# TSC_AD7843.net
KiCad netlist of a schematic drawn in Altium Designer
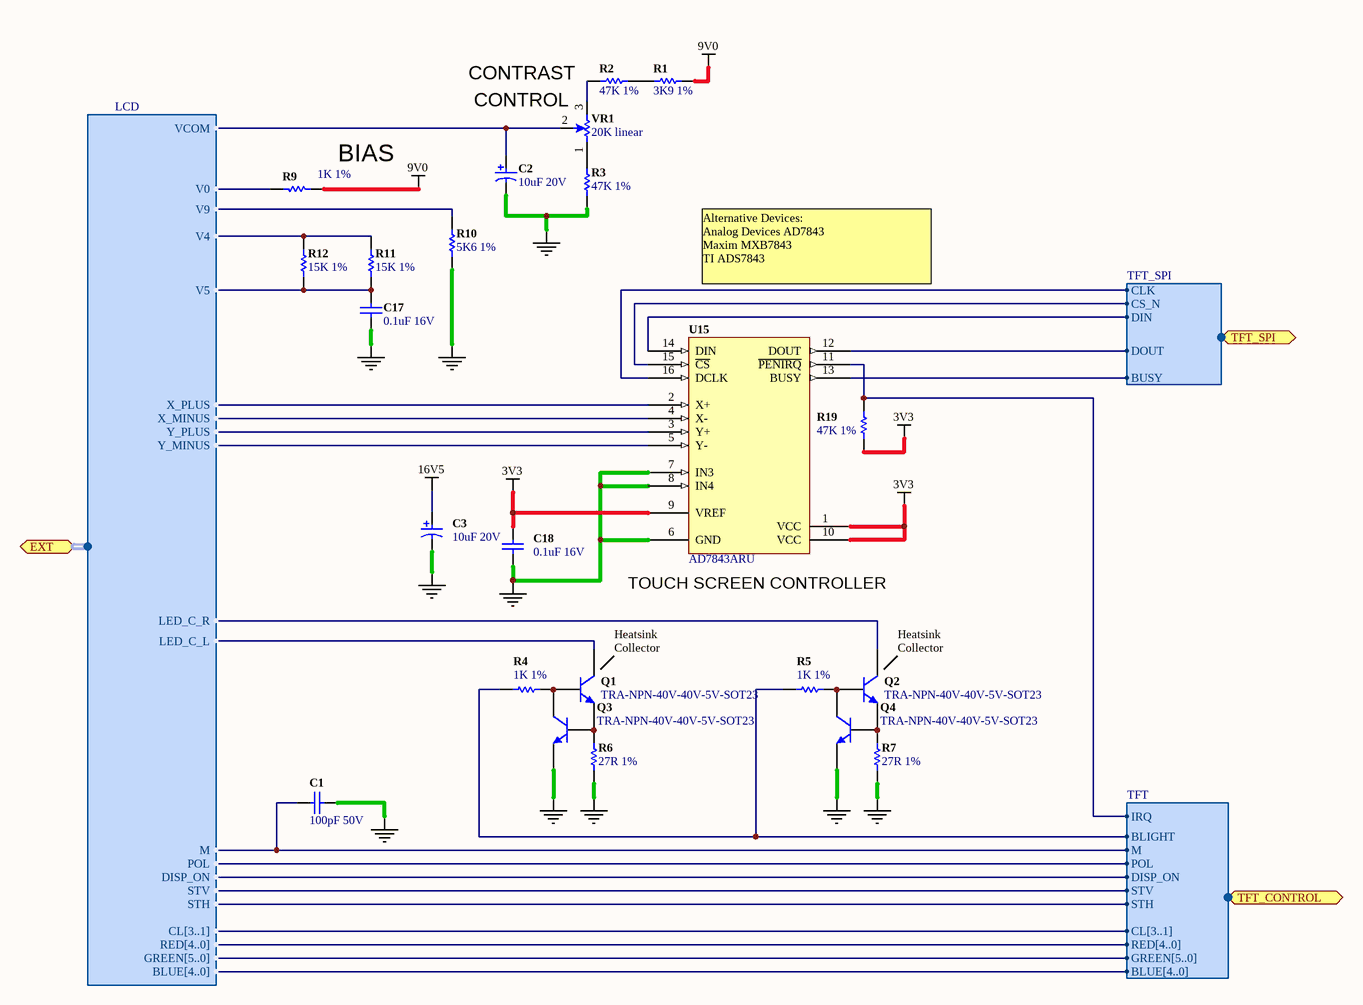
[diagram p0: TSC_AD7843.SchDoc]

(export (version "E")
  (design (tool "Eeschema 10.0.6"))
  (components
    (comp (ref "C1")
      (value "100pF 50V")
      (footprint "CAPC1005-STAR")
      (description "Capacitor, Ceramic, 100pF 5% 50V 0402 (1005) COG")
      (fields (field (name "TOLERANCE") "5 %"))
      (libsource (lib "altium-import") (part "root_3_mirrored_CAP-NP_"))
    )
    (comp (ref "C2")
      (value "10uF 20V")
      (footprint "CAPC3528-STAR")
      (description "Capacitor, Tantalum, 10uF 10% 20V MCCT-B (3528)")
      (fields (field (name "TOLERANCE") "10 %"))
      (libsource (lib "altium-import") (part "root_0_CAP-P_"))
    )
    (comp (ref "C3")
      (value "10uF 20V")
      (footprint "CAPC3528-STAR")
      (description "Capacitor, Tantalum, 10uF 10% 20V MCCT-B (3528)")
      (fields (field (name "TOLERANCE") "10 %"))
      (libsource (lib "altium-import") (part "root_0_CAP-P_"))
    )
    (comp (ref "C17")
      (value "0.1uF 16V")
      (footprint "CAPC1005-STAR")
      (description "Capacitor, Ceramic, 0.1uF 10% 16V 0402 (1005) X7R")
      (fields (field (name "TOLERANCE") "10 %"))
      (libsource (lib "altium-import") (part "root_0_mirrored_CAP-NP_"))
    )
    (comp (ref "C18")
      (value "0.1uF 16V")
      (footprint "CAPC1005-STAR")
      (description "Capacitor, Ceramic, 0.1uF 10% 16V 0402 (1005) X7R")
      (fields (field (name "TOLERANCE") "10 %"))
      (libsource (lib "altium-import") (part "root_0_CAP-NP_"))
    )
    (comp (ref "Q1")
      (value "TRA-NPN-40V-40V-5V-SOT23")
      (footprint "SOT95P230-3C")
      (description "Transistor, FMMT491A Small Signal NPN")
      (libsource (lib "altium-import") (part "root_0_TRA-NPN_"))
    )
    (comp (ref "Q2")
      (value "TRA-NPN-40V-40V-5V-SOT23")
      (footprint "SOT95P230-3C")
      (description "Transistor, FMMT491A Small Signal NPN")
      (libsource (lib "altium-import") (part "root_0_TRA-NPN_"))
    )
    (comp (ref "Q3")
      (value "TRA-NPN-40V-40V-5V-SOT23")
      (footprint "SOT95P230-3C")
      (description "Transistor, FMMT491A Small Signal NPN")
      (libsource (lib "altium-import") (part "root_0_mirrored_TRA-NPN_"))
    )
    (comp (ref "Q4")
      (value "TRA-NPN-40V-40V-5V-SOT23")
      (footprint "SOT95P230-3C")
      (description "Transistor, FMMT491A Small Signal NPN")
      (libsource (lib "altium-import") (part "root_0_mirrored_TRA-NPN_"))
    )
    (comp (ref "R1")
      (value "3K9 1%")
      (footprint "RESC1005-STAR")
      (description "Resistor, 3K9 1% 0402 (1005)")
      (fields (field (name "TOLERANCE") "1 %"))
      (libsource (lib "altium-import") (part "root_1_RES_"))
    )
    (comp (ref "R2")
      (value "47K 1%")
      (footprint "RESC1005-STAR")
      (description "Resistor, 47K 1% 0402 (1005)")
      (fields (field (name "TOLERANCE") "1 %"))
      (libsource (lib "altium-import") (part "root_1_RES_"))
    )
    (comp (ref "R3")
      (value "47K 1%")
      (footprint "RESC1005-STAR")
      (description "Resistor, 47K 1% 0402 (1005)")
      (fields (field (name "TOLERANCE") "1 %"))
      (libsource (lib "altium-import") (part "root_2_RES_"))
    )
    (comp (ref "R4")
      (value "1K 1%")
      (footprint "RESC1005-STAR")
      (description "Resistor, 1K 1% 0402 (1005)")
      (fields (field (name "TOLERANCE") "1 %"))
      (libsource (lib "altium-import") (part "root_1_RES_"))
    )
    (comp (ref "R5")
      (value "1K 1%")
      (footprint "RESC1005-STAR")
      (description "Resistor, 1K 1% 0402 (1005)")
      (fields (field (name "TOLERANCE") "1 %"))
      (libsource (lib "altium-import") (part "root_1_RES_"))
    )
    (comp (ref "R6")
      (value "27R 1%")
      (footprint "RESC1005-STAR")
      (description "Resistor, 27R 1% 0402 (1005)")
      (fields (field (name "TOLERANCE") "1 %"))
      (libsource (lib "altium-import") (part "root_2_RES_"))
    )
    (comp (ref "R7")
      (value "27R 1%")
      (footprint "RESC1005-STAR")
      (description "Resistor, 27R 1% 0402 (1005)")
      (fields (field (name "TOLERANCE") "1 %"))
      (libsource (lib "altium-import") (part "root_2_RES_"))
    )
    (comp (ref "R9")
      (value "1K 1%")
      (footprint "RESC1005-STAR")
      (description "Resistor, 1K 1% 0402 (1005)")
      (fields (field (name "TOLERANCE") "1 %"))
      (libsource (lib "altium-import") (part "root_3_mirrored_RES_"))
    )
    (comp (ref "R10")
      (value "5K6 1%")
      (footprint "RESC1005-STAR")
      (description "Resistor, 5K6 1% 0402 (1005)")
      (fields (field (name "TOLERANCE") "1 %"))
      (libsource (lib "altium-import") (part "root_2_RES_"))
    )
    (comp (ref "R11")
      (value "15K 1%")
      (footprint "RESC1005-STAR")
      (description "Resistor, 15K 1% 0402 (1005)")
      (fields (field (name "TOLERANCE") "1 %"))
      (libsource (lib "altium-import") (part "root_2_RES_"))
    )
    (comp (ref "R12")
      (value "15K 1%")
      (footprint "RESC1005-STAR")
      (description "Resistor, 15K 1% 0402 (1005)")
      (fields (field (name "TOLERANCE") "1 %"))
      (libsource (lib "altium-import") (part "root_2_RES_"))
    )
    (comp (ref "R19")
      (value "47K 1%")
      (footprint "RESC1005-STAR")
      (description "Resistor, 47K 1% 0402 (1005)")
      (fields (field (name "TOLERANCE") "1 %"))
      (libsource (lib "altium-import") (part "root_0_RES_"))
    )
    (comp (ref "U15")
      (value "AD7843ARU")
      (footprint "TSOP65P638-16")
      (description "AD7843ARU,12-bit SPI Touch Screen Digitizer")
      (libsource (lib "altium-import") (part "root_0_AD7843ARU_"))
    )
    (comp (ref "VR1")
      (value "20K linear")
      (footprint "TRIM_3314J-1-203E")
      (description "Potentiometer, 20K 4mm Cermet PCB SMT Trimmer")
      (libsource (lib "altium-import") (part "root_2_mirrored_POT_"))
    )
  )
  (nets
    (net (code "5") (name "/BLIGHT") (class "Default")
      (node (ref "R4") (pin "1") (pinfunction "1_1") (pintype "passive"))
      (node (ref "R5") (pin "1") (pinfunction "1_1") (pintype "passive"))
    )
    (net (code "6") (name "/BUSY") (class "Default")
      (node (ref "U15") (pin "13") (pinfunction "BUSY_13") (pintype "output"))
    )
    (net (code "7") (name "/CLK") (class "Default")
      (node (ref "U15") (pin "16") (pinfunction "DCLK_16") (pintype "input"))
    )
    (net (code "8") (name "/CS_N") (class "Default")
      (node (ref "U15") (pin "15") (pinfunction "~{CS}_15") (pintype "input"))
    )
    (net (code "9") (name "/DIN") (class "Default")
      (node (ref "U15") (pin "14") (pinfunction "DIN_14") (pintype "input"))
    )
    (net (code "11") (name "/DOUT") (class "Default")
      (node (ref "U15") (pin "12") (pinfunction "DOUT_12") (pintype "output"))
    )
    (net (code "13") (name "/IRQ") (class "Default")
      (node (ref "R19") (pin "1") (pinfunction "1_1") (pintype "passive"))
      (node (ref "U15") (pin "11") (pinfunction "~{PENIRQ}_11") (pintype "output"))
    )
    (net (code "14") (name "/LED_C_L") (class "Default")
      (node (ref "Q1") (pin "3") (pinfunction "C_3") (pintype "passive"))
    )
    (net (code "15") (name "/LED_C_R") (class "Default")
      (node (ref "Q2") (pin "3") (pinfunction "C_3") (pintype "passive"))
    )
    (net (code "16") (name "/M") (class "Default")
      (node (ref "C1") (pin "1") (pinfunction "1_1") (pintype "passive"))
    )
    (net (code "21") (name "/V0") (class "Default")
      (node (ref "R9") (pin "1") (pinfunction "1_1") (pintype "passive"))
    )
    (net (code "22") (name "/V4") (class "Default")
      (node (ref "R11") (pin "2") (pinfunction "2_2") (pintype "passive"))
      (node (ref "R12") (pin "2") (pinfunction "2_2") (pintype "passive"))
    )
    (net (code "23") (name "/V5") (class "Default")
      (node (ref "C17") (pin "1") (pinfunction "1_1") (pintype "passive"))
      (node (ref "R11") (pin "1") (pinfunction "1_1") (pintype "passive"))
      (node (ref "R12") (pin "1") (pinfunction "1_1") (pintype "passive"))
    )
    (net (code "24") (name "/V9") (class "Default")
      (node (ref "R10") (pin "2") (pinfunction "2_2") (pintype "passive"))
    )
    (net (code "25") (name "/VCOM") (class "Default")
      (node (ref "C2") (pin "1") (pinfunction "1_1") (pintype "passive"))
      (node (ref "VR1") (pin "2") (pinfunction "2_2") (pintype "passive"))
    )
    (net (code "26") (name "/X_MINUS") (class "Default")
      (node (ref "U15") (pin "4") (pinfunction "X-_4") (pintype "input"))
    )
    (net (code "27") (name "/X_PLUS") (class "Default")
      (node (ref "U15") (pin "2") (pinfunction "X+_2") (pintype "input"))
    )
    (net (code "28") (name "/Y_MINUS") (class "Default")
      (node (ref "U15") (pin "5") (pinfunction "Y-_5") (pintype "input"))
    )
    (net (code "29") (name "/Y_PLUS") (class "Default")
      (node (ref "U15") (pin "3") (pinfunction "Y+_3") (pintype "input"))
    )
    (net (code "32") (name "3V3") (class "Default")
      (node (ref "C18") (pin "1") (pinfunction "1_1") (pintype "passive"))
      (node (ref "R19") (pin "2") (pinfunction "2_2") (pintype "passive"))
      (node (ref "U15") (pin "1") (pinfunction "VCC_1") (pintype "power_in"))
      (node (ref "U15") (pin "10") (pinfunction "VCC_10") (pintype "power_in"))
      (node (ref "U15") (pin "9") (pinfunction "VREF_9") (pintype "passive"))
    )
    (net (code "33") (name "9V0") (class "Default")
      (node (ref "R1") (pin "2") (pinfunction "2_2") (pintype "passive"))
      (node (ref "R9") (pin "2") (pinfunction "2_2") (pintype "passive"))
    )
    (net (code "34") (name "16V5") (class "Default")
      (node (ref "C3") (pin "1") (pinfunction "1_1") (pintype "passive"))
    )
    (net (code "35") (name "GND") (class "Default")
      (node (ref "C1") (pin "2") (pinfunction "2_2") (pintype "passive"))
      (node (ref "C17") (pin "2") (pinfunction "2_2") (pintype "passive"))
      (node (ref "C18") (pin "2") (pinfunction "2_2") (pintype "passive"))
      (node (ref "C2") (pin "2") (pinfunction "2_2") (pintype "passive"))
      (node (ref "C3") (pin "2") (pinfunction "2_2") (pintype "passive"))
      (node (ref "Q3") (pin "2") (pinfunction "E_2") (pintype "passive"))
      (node (ref "Q4") (pin "2") (pinfunction "E_2") (pintype "passive"))
      (node (ref "R10") (pin "1") (pinfunction "1_1") (pintype "passive"))
      (node (ref "R3") (pin "1") (pinfunction "1_1") (pintype "passive"))
      (node (ref "R6") (pin "1") (pinfunction "1_1") (pintype "passive"))
      (node (ref "R7") (pin "1") (pinfunction "1_1") (pintype "passive"))
      (node (ref "U15") (pin "6") (pinfunction "GND_6") (pintype "power_in"))
      (node (ref "U15") (pin "7") (pinfunction "IN3_7") (pintype "input"))
      (node (ref "U15") (pin "8") (pinfunction "IN4_8") (pintype "input"))
    )
    (net (code "36") (name "Net-(Q1-B)") (class "Default")
      (node (ref "Q1") (pin "1") (pinfunction "B_1") (pintype "passive"))
      (node (ref "Q3") (pin "3") (pinfunction "C_3") (pintype "passive"))
      (node (ref "R4") (pin "2") (pinfunction "2_2") (pintype "passive"))
    )
    (net (code "37") (name "Net-(Q1-E)") (class "Default")
      (node (ref "Q1") (pin "2") (pinfunction "E_2") (pintype "passive"))
      (node (ref "Q3") (pin "1") (pinfunction "B_1") (pintype "passive"))
      (node (ref "R6") (pin "2") (pinfunction "2_2") (pintype "passive"))
    )
    (net (code "38") (name "Net-(Q2-B)") (class "Default")
      (node (ref "Q2") (pin "1") (pinfunction "B_1") (pintype "passive"))
      (node (ref "Q4") (pin "3") (pinfunction "C_3") (pintype "passive"))
      (node (ref "R5") (pin "2") (pinfunction "2_2") (pintype "passive"))
    )
    (net (code "39") (name "Net-(Q2-E)") (class "Default")
      (node (ref "Q2") (pin "2") (pinfunction "E_2") (pintype "passive"))
      (node (ref "Q4") (pin "1") (pinfunction "B_1") (pintype "passive"))
      (node (ref "R7") (pin "2") (pinfunction "2_2") (pintype "passive"))
    )
    (net (code "40") (name "Net-(R1-Pad1)") (class "Default")
      (node (ref "R1") (pin "1") (pinfunction "1_1") (pintype "passive"))
      (node (ref "R2") (pin "2") (pinfunction "2_2") (pintype "passive"))
    )
    (net (code "41") (name "Net-(R2-Pad1)") (class "Default")
      (node (ref "R2") (pin "1") (pinfunction "1_1") (pintype "passive"))
      (node (ref "VR1") (pin "3") (pinfunction "3_3") (pintype "passive"))
    )
    (net (code "42") (name "Net-(R3-Pad2)") (class "Default")
      (node (ref "R3") (pin "2") (pinfunction "2_2") (pintype "passive"))
      (node (ref "VR1") (pin "1") (pinfunction "1_1") (pintype "passive"))
    )
  )
)
